# untitled.net
KiCad netlist of a schematic drawn in EAGLE
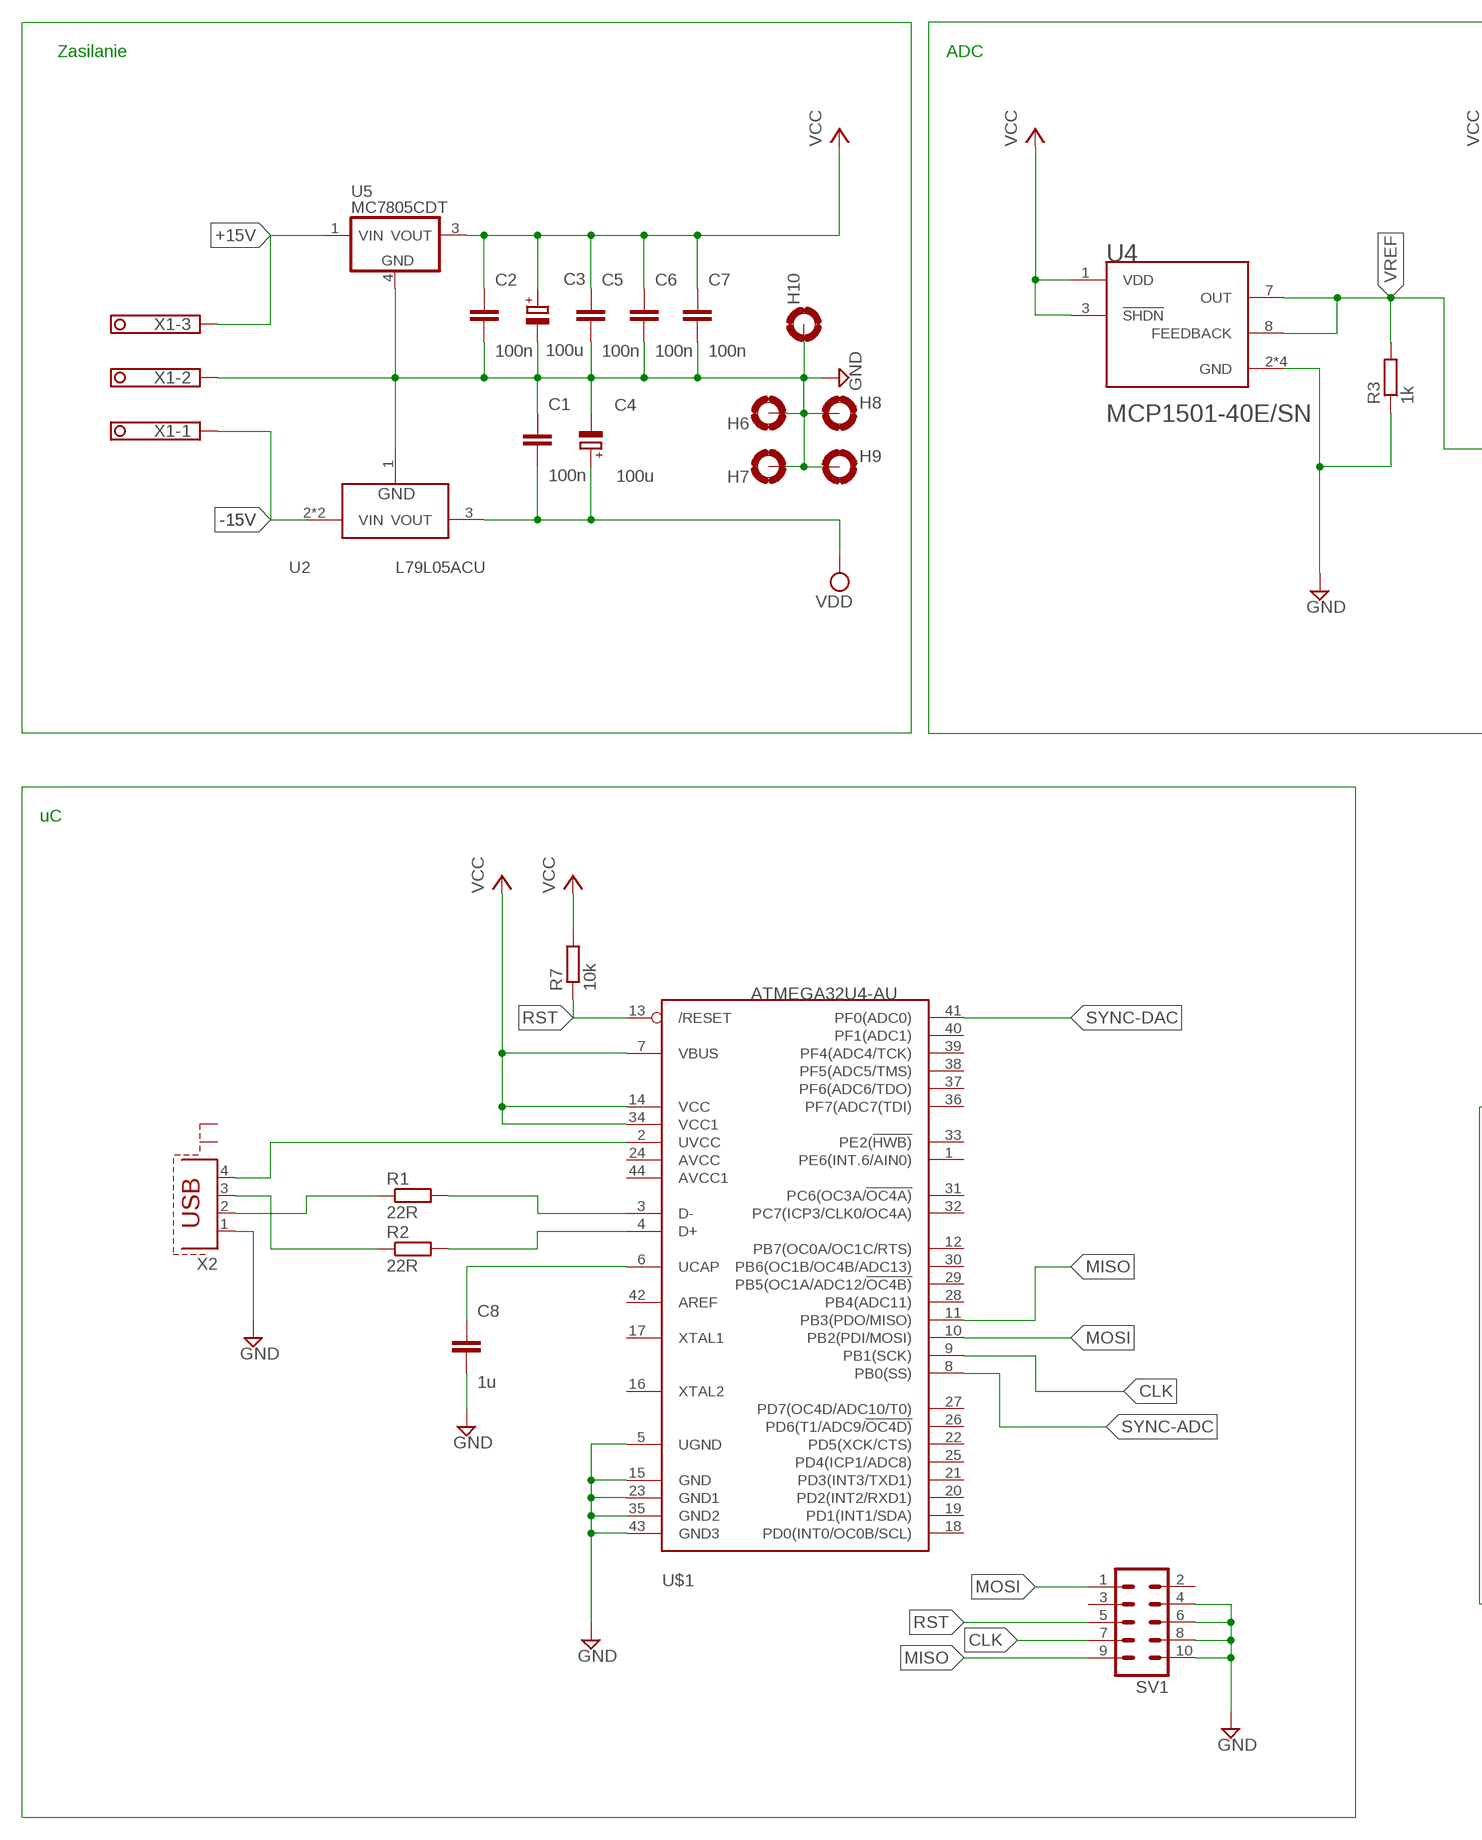
[diagram p0: schematic, sheet 1, part 1 of 2]
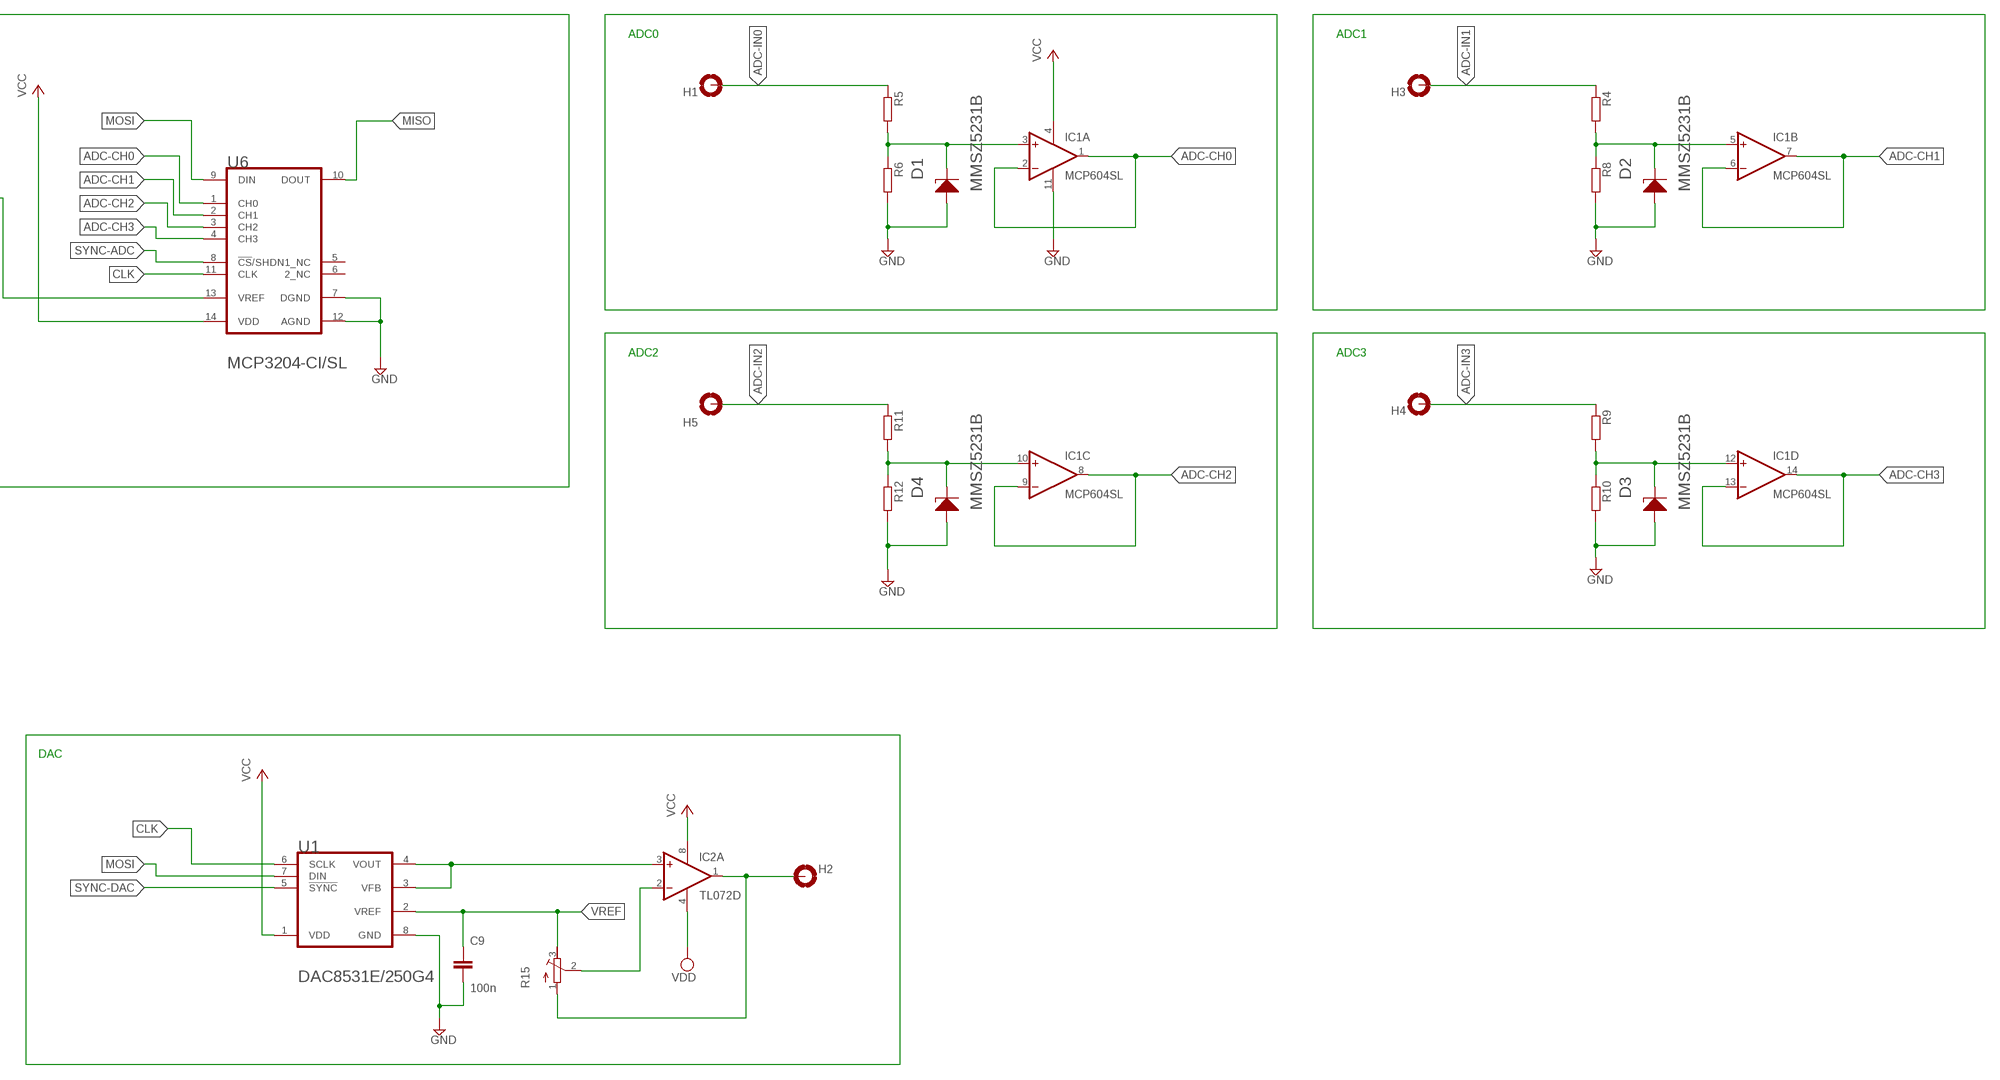
[diagram p1: schematic, sheet 1, part 2 of 2]

(export (version "E")
  (design (tool "Eeschema 10.0.6"))
  (components
    (comp (ref "C1")
      (value "100n")
      (footprint "eagle-import:C0805K")
      (libsource (lib "eagle-import") (part "C-EUC0805K"))
    )
    (comp (ref "C2")
      (value "100n")
      (footprint "eagle-import:C0805K")
      (libsource (lib "eagle-import") (part "C-EUC0805K"))
    )
    (comp (ref "C3")
      (value "100u")
      (footprint "eagle-import:153CLV-1014")
      (libsource (lib "eagle-import") (part "CPOL-EU153CLV-1014"))
    )
    (comp (ref "C4")
      (value "100u")
      (footprint "eagle-import:153CLV-1014")
      (libsource (lib "eagle-import") (part "CPOL-EU153CLV-1014"))
    )
    (comp (ref "C5")
      (value "100n")
      (footprint "eagle-import:C0805K")
      (libsource (lib "eagle-import") (part "C-EUC0805K"))
    )
    (comp (ref "C6")
      (value "100n")
      (footprint "eagle-import:C0805K")
      (libsource (lib "eagle-import") (part "C-EUC0805K"))
    )
    (comp (ref "C7")
      (value "100n")
      (footprint "eagle-import:C0805K")
      (libsource (lib "eagle-import") (part "C-EUC0805K"))
    )
    (comp (ref "C8")
      (value "1u")
      (footprint "eagle-import:C0805K")
      (libsource (lib "eagle-import") (part "C-EUC0805K"))
    )
    (comp (ref "C9")
      (value "100n")
      (footprint "eagle-import:C0805K")
      (libsource (lib "eagle-import") (part "C-EUC0805K"))
    )
    (comp (ref "D1")
      (value "MMSZ5231BVISHAY_SEMICONDUCTOR_MMSZ5231B-E3-08_0_0")
      (footprint "eagle-import:VISHAY_SEMICONDUCTOR_MMSZ5231B-E3-08_0")
      (fields
        (field (name "MF") "Vishay Semiconductor")
        (field (name "MPN") "MMSZ5231B-E3-08")
        (field (name "TOLERANCE") "+/- 5%")
      )
      (libsource (lib "eagle-import") (part "MMSZ5231BVISHAY_SEMICONDUCTOR_MMSZ5231B-E3-08_0_0"))
    )
    (comp (ref "D2")
      (value "MMSZ5231BVISHAY_SEMICONDUCTOR_MMSZ5231B-E3-08_0_0")
      (footprint "eagle-import:VISHAY_SEMICONDUCTOR_MMSZ5231B-E3-08_0")
      (fields
        (field (name "MF") "Vishay Semiconductor")
        (field (name "MPN") "MMSZ5231B-E3-08")
        (field (name "TOLERANCE") "+/- 5%")
      )
      (libsource (lib "eagle-import") (part "MMSZ5231BVISHAY_SEMICONDUCTOR_MMSZ5231B-E3-08_0_0"))
    )
    (comp (ref "D3")
      (value "MMSZ5231BVISHAY_SEMICONDUCTOR_MMSZ5231B-E3-08_0_0")
      (footprint "eagle-import:VISHAY_SEMICONDUCTOR_MMSZ5231B-E3-08_0")
      (fields
        (field (name "MF") "Vishay Semiconductor")
        (field (name "MPN") "MMSZ5231B-E3-08")
        (field (name "TOLERANCE") "+/- 5%")
      )
      (libsource (lib "eagle-import") (part "MMSZ5231BVISHAY_SEMICONDUCTOR_MMSZ5231B-E3-08_0_0"))
    )
    (comp (ref "D4")
      (value "MMSZ5231BVISHAY_SEMICONDUCTOR_MMSZ5231B-E3-08_0_0")
      (footprint "eagle-import:VISHAY_SEMICONDUCTOR_MMSZ5231B-E3-08_0")
      (fields
        (field (name "MF") "Vishay Semiconductor")
        (field (name "MPN") "MMSZ5231B-E3-08")
        (field (name "TOLERANCE") "+/- 5%")
      )
      (libsource (lib "eagle-import") (part "MMSZ5231BVISHAY_SEMICONDUCTOR_MMSZ5231B-E3-08_0_0"))
    )
    (comp (ref "H1")
      (value "MOUNT-PAD-ROUND2.8")
      (footprint "eagle-import:2,8-PAD")
      (libsource (lib "eagle-import") (part "MOUNT-PAD-ROUND2.8"))
    )
    (comp (ref "H2")
      (value "MOUNT-PAD-ROUND2.8")
      (footprint "eagle-import:2,8-PAD")
      (libsource (lib "eagle-import") (part "MOUNT-PAD-ROUND2.8"))
    )
    (comp (ref "H3")
      (value "MOUNT-PAD-ROUND2.8")
      (footprint "eagle-import:2,8-PAD")
      (libsource (lib "eagle-import") (part "MOUNT-PAD-ROUND2.8"))
    )
    (comp (ref "H4")
      (value "MOUNT-PAD-ROUND2.8")
      (footprint "eagle-import:2,8-PAD")
      (libsource (lib "eagle-import") (part "MOUNT-PAD-ROUND2.8"))
    )
    (comp (ref "H5")
      (value "MOUNT-PAD-ROUND2.8")
      (footprint "eagle-import:2,8-PAD")
      (libsource (lib "eagle-import") (part "MOUNT-PAD-ROUND2.8"))
    )
    (comp (ref "H6")
      (value "MOUNT-PAD-ROUND2.8")
      (footprint "eagle-import:2,8-PAD")
      (libsource (lib "eagle-import") (part "MOUNT-PAD-ROUND2.8"))
    )
    (comp (ref "H7")
      (value "MOUNT-PAD-ROUND2.8")
      (footprint "eagle-import:2,8-PAD")
      (libsource (lib "eagle-import") (part "MOUNT-PAD-ROUND2.8"))
    )
    (comp (ref "H8")
      (value "MOUNT-PAD-ROUND2.8")
      (footprint "eagle-import:2,8-PAD")
      (libsource (lib "eagle-import") (part "MOUNT-PAD-ROUND2.8"))
    )
    (comp (ref "H9")
      (value "MOUNT-PAD-ROUND2.8")
      (footprint "eagle-import:2,8-PAD")
      (libsource (lib "eagle-import") (part "MOUNT-PAD-ROUND2.8"))
    )
    (comp (ref "H10")
      (value "MOUNT-PAD-ROUND2.8")
      (footprint "eagle-import:2,8-PAD")
      (libsource (lib "eagle-import") (part "MOUNT-PAD-ROUND2.8"))
    )
    (comp (ref "IC1")
      (value "MCP604SL")
      (footprint "eagle-import:SO14")
      (libsource (lib "eagle-import") (part "MCP604SL"))
    )
    (comp (ref "IC2")
      (value "TL072D")
      (footprint "eagle-import:SO08")
      (fields (field (name "SPICEPREFIX") "J"))
      (libsource (lib "eagle-import") (part "TL072D"))
    )
    (comp (ref "R1")
      (value "22R")
      (footprint "eagle-import:R1206")
      (libsource (lib "eagle-import") (part "R-EU_R1206"))
    )
    (comp (ref "R2")
      (value "22R")
      (footprint "eagle-import:R1206")
      (libsource (lib "eagle-import") (part "R-EU_R1206"))
    )
    (comp (ref "R3")
      (value "1k")
      (footprint "eagle-import:M1206")
      (libsource (lib "eagle-import") (part "R-EU_M1206"))
    )
    (comp (ref "R4")
      (value "R-EU_M1206")
      (footprint "eagle-import:M1206")
      (libsource (lib "eagle-import") (part "R-EU_M1206"))
    )
    (comp (ref "R5")
      (value "R-EU_M1206")
      (footprint "eagle-import:M1206")
      (libsource (lib "eagle-import") (part "R-EU_M1206"))
    )
    (comp (ref "R6")
      (value "R-EU_M1206")
      (footprint "eagle-import:M1206")
      (libsource (lib "eagle-import") (part "R-EU_M1206"))
    )
    (comp (ref "R7")
      (value "10k")
      (footprint "eagle-import:M1206")
      (libsource (lib "eagle-import") (part "R-EU_M1206"))
    )
    (comp (ref "R8")
      (value "R-EU_M1206")
      (footprint "eagle-import:M1206")
      (libsource (lib "eagle-import") (part "R-EU_M1206"))
    )
    (comp (ref "R9")
      (value "R-EU_M1206")
      (footprint "eagle-import:M1206")
      (libsource (lib "eagle-import") (part "R-EU_M1206"))
    )
    (comp (ref "R10")
      (value "R-EU_M1206")
      (footprint "eagle-import:M1206")
      (libsource (lib "eagle-import") (part "R-EU_M1206"))
    )
    (comp (ref "R11")
      (value "R-EU_M1206")
      (footprint "eagle-import:M1206")
      (libsource (lib "eagle-import") (part "R-EU_M1206"))
    )
    (comp (ref "R12")
      (value "R-EU_M1206")
      (footprint "eagle-import:M1206")
      (libsource (lib "eagle-import") (part "R-EU_M1206"))
    )
    (comp (ref "R15")
      (value "R-TRIMM64Y")
      (footprint "eagle-import:RTRIM64Y")
      (libsource (lib "eagle-import") (part "R-TRIMM64Y"))
    )
    (comp (ref "SV1")
      (value "ML10")
      (footprint "eagle-import:ML10")
      (libsource (lib "eagle-import") (part "ML10"))
    )
    (comp (ref "U$1")
      (value "ATMEGA32U4-AU")
      (footprint "eagle-import:TQFP44")
      (libsource (lib "eagle-import") (part "ATMEGA32U4-AU"))
    )
    (comp (ref "U1")
      (value "TEXAS_INSTRUMENTS_DAC8531E-250G4TEXAS_INSTRUMENTS_DAC8531E-250G4_0_0")
      (footprint "eagle-import:TEXAS_INSTRUMENTS_DAC8531E-250G4_0")
      (fields (field (name "MF") "Texas Instruments") (field (name "MPN") "DAC8531E/250G4"))
      (libsource (lib "eagle-import") (part "TEXAS_INSTRUMENTS_DAC8531E-250G4TEXAS_INSTRUMENTS_DAC8531E-250G4_0_0"))
    )
    (comp (ref "U2")
      (value "L79L05ACUTRL79L05ACU")
      (footprint "eagle-import:L79L05ACUTR_1")
      (fields
        (field (name "MF") "STMicroelectronics")
        (field (name "MPN") "L79L05ACUTR")
        (field (name "SPICEPREFIX") "U")
      )
      (libsource (lib "eagle-import") (part "L79L05ACUTRL79L05ACU"))
    )
    (comp (ref "U4")
      (value "MCP1501-40E/SN")
      (footprint "eagle-import:SOIC127P600X175-8N")
      (fields (field (name "MF") "Microchip"))
      (libsource (lib "eagle-import") (part "MCP1501-40E/SN"))
    )
    (comp (ref "U5")
      (value "MC7805CDT")
      (footprint "eagle-import:DPAK-3")
      (libsource (lib "eagle-import") (part "MC78DT05C"))
    )
    (comp (ref "U6")
      (value "MCP3204-CI-SL")
      (footprint "eagle-import:SO14")
      (libsource (lib "eagle-import") (part "MCP3204-CI-SL"))
    )
    (comp (ref "X1")
      (value "1751251")
      (footprint "eagle-import:1751251")
      (libsource (lib "eagle-import") (part "1751251"))
    )
    (comp (ref "X2")
      (value "PN61729-S")
      (footprint "eagle-import:PN61729-S")
      (libsource (lib "eagle-import") (part "PN61729-S"))
    )
  )
  (nets
    (net (code "1") (name "+15V") (class "Default")
      (node (ref "U5") (pin "1") (pinfunction "VIN_1") (pintype "power_in"))
      (node (ref "X1") (pin "3") (pinfunction "K_3") (pintype "passive"))
    )
    (net (code "2") (name "-15V") (class "Default")
      (node (ref "U2") (pin "2") (pinfunction "VIN_2") (pintype "power_in"))
      (node (ref "U2") (pin "2-2") (pinfunction "VIN_2-2") (pintype "power_in"))
      (node (ref "X1") (pin "1") (pinfunction "K_1") (pintype "passive"))
    )
    (net (code "3") (name "ADC-CH0") (class "Default")
      (node (ref "IC1") (pin "1") (pinfunction "OUT_1") (pintype "output"))
      (node (ref "IC1") (pin "2") (pinfunction "-IN_2") (pintype "input"))
      (node (ref "U6") (pin "1") (pinfunction "CH0_1") (pintype "input"))
    )
    (net (code "4") (name "ADC-CH1") (class "Default")
      (node (ref "IC1") (pin "6") (pinfunction "-IN_6") (pintype "input"))
      (node (ref "IC1") (pin "7") (pinfunction "OUT_7") (pintype "output"))
      (node (ref "U6") (pin "2") (pinfunction "CH1_2") (pintype "input"))
    )
    (net (code "5") (name "ADC-CH2") (class "Default")
      (node (ref "IC1") (pin "8") (pinfunction "OUT_8") (pintype "output"))
      (node (ref "IC1") (pin "9") (pinfunction "-IN_9") (pintype "input"))
      (node (ref "U6") (pin "3") (pinfunction "CH2_3") (pintype "input"))
    )
    (net (code "6") (name "ADC-CH3") (class "Default")
      (node (ref "IC1") (pin "13") (pinfunction "-IN_13") (pintype "input"))
      (node (ref "IC1") (pin "14") (pinfunction "OUT_14") (pintype "output"))
      (node (ref "U6") (pin "4") (pinfunction "CH3_4") (pintype "input"))
    )
    (net (code "7") (name "ADC-IN0") (class "Default")
      (node (ref "H1") (pin "B2,8") (pinfunction "MOUNT_B2,8") (pintype "passive"))
      (node (ref "R5") (pin "1") (pinfunction "1_1") (pintype "passive"))
    )
    (net (code "8") (name "ADC-IN1") (class "Default")
      (node (ref "H3") (pin "B2,8") (pinfunction "MOUNT_B2,8") (pintype "passive"))
      (node (ref "R4") (pin "1") (pinfunction "1_1") (pintype "passive"))
    )
    (net (code "9") (name "ADC-IN2") (class "Default")
      (node (ref "H5") (pin "B2,8") (pinfunction "MOUNT_B2,8") (pintype "passive"))
      (node (ref "R11") (pin "1") (pinfunction "1_1") (pintype "passive"))
    )
    (net (code "10") (name "ADC-IN3") (class "Default")
      (node (ref "H4") (pin "B2,8") (pinfunction "MOUNT_B2,8") (pintype "passive"))
      (node (ref "R9") (pin "1") (pinfunction "1_1") (pintype "passive"))
    )
    (net (code "11") (name "CLK") (class "Default")
      (node (ref "SV1") (pin "7") (pinfunction "7_7") (pintype "passive"))
      (node (ref "U$1") (pin "9") (pinfunction "PB1(SCK)_9") (pintype "bidirectional"))
      (node (ref "U1") (pin "6") (pinfunction "SCLK_6") (pintype "input"))
      (node (ref "U6") (pin "11") (pinfunction "CLK_11") (pintype "input"))
    )
    (net (code "12") (name "GND") (class "Default")
      (node (ref "C1") (pin "1") (pinfunction "1_1") (pintype "passive"))
      (node (ref "C2") (pin "2") (pinfunction "2_2") (pintype "passive"))
      (node (ref "C3") (pin "-") (pinfunction "-_-") (pintype "passive"))
      (node (ref "C4") (pin "-") (pinfunction "-_-") (pintype "passive"))
      (node (ref "C5") (pin "2") (pinfunction "2_2") (pintype "passive"))
      (node (ref "C6") (pin "2") (pinfunction "2_2") (pintype "passive"))
      (node (ref "C7") (pin "2") (pinfunction "2_2") (pintype "passive"))
      (node (ref "C8") (pin "2") (pinfunction "2_2") (pintype "passive"))
      (node (ref "C9") (pin "2") (pinfunction "2_2") (pintype "passive"))
      (node (ref "D1") (pin "1") (pinfunction "A_1") (pintype "passive"))
      (node (ref "D2") (pin "1") (pinfunction "A_1") (pintype "passive"))
      (node (ref "D3") (pin "1") (pinfunction "A_1") (pintype "passive"))
      (node (ref "D4") (pin "1") (pinfunction "A_1") (pintype "passive"))
      (node (ref "H10") (pin "B2,8") (pinfunction "MOUNT_B2,8") (pintype "passive"))
      (node (ref "H6") (pin "B2,8") (pinfunction "MOUNT_B2,8") (pintype "passive"))
      (node (ref "H7") (pin "B2,8") (pinfunction "MOUNT_B2,8") (pintype "passive"))
      (node (ref "H8") (pin "B2,8") (pinfunction "MOUNT_B2,8") (pintype "passive"))
      (node (ref "H9") (pin "B2,8") (pinfunction "MOUNT_B2,8") (pintype "passive"))
      (node (ref "IC1") (pin "11") (pinfunction "V-_11") (pintype "power_in"))
      (node (ref "R10") (pin "2") (pinfunction "2_2") (pintype "passive"))
      (node (ref "R12") (pin "2") (pinfunction "2_2") (pintype "passive"))
      (node (ref "R3") (pin "1") (pinfunction "1_1") (pintype "passive"))
      (node (ref "R6") (pin "2") (pinfunction "2_2") (pintype "passive"))
      (node (ref "R8") (pin "2") (pinfunction "2_2") (pintype "passive"))
      (node (ref "SV1") (pin "10") (pinfunction "10_10") (pintype "passive"))
      (node (ref "SV1") (pin "4") (pinfunction "4_4") (pintype "passive"))
      (node (ref "SV1") (pin "6") (pinfunction "6_6") (pintype "passive"))
      (node (ref "SV1") (pin "8") (pinfunction "8_8") (pintype "passive"))
      (node (ref "U$1") (pin "15") (pinfunction "GND_15") (pintype "bidirectional"))
      (node (ref "U$1") (pin "23") (pinfunction "GND1_23") (pintype "bidirectional"))
      (node (ref "U$1") (pin "35") (pinfunction "GND2_35") (pintype "bidirectional"))
      (node (ref "U$1") (pin "43") (pinfunction "GND3_43") (pintype "bidirectional"))
      (node (ref "U$1") (pin "5") (pinfunction "UGND_5") (pintype "bidirectional"))
      (node (ref "U1") (pin "8") (pinfunction "GND_8") (pintype "power_in"))
      (node (ref "U2") (pin "1") (pinfunction "GND_1") (pintype "power_in"))
      (node (ref "U4") (pin "2") (pinfunction "GND_2") (pintype "passive"))
      (node (ref "U4") (pin "4") (pinfunction "GND_4") (pintype "passive"))
      (node (ref "U4") (pin "5") (pinfunction "GND_5") (pintype "passive"))
      (node (ref "U4") (pin "6") (pinfunction "GND_6") (pintype "passive"))
      (node (ref "U5") (pin "4") (pinfunction "GND_4") (pintype "power_in"))
      (node (ref "U6") (pin "12") (pinfunction "AGND_12") (pintype "power_in"))
      (node (ref "U6") (pin "7") (pinfunction "DGND_7") (pintype "power_in"))
      (node (ref "X1") (pin "2") (pinfunction "K_2") (pintype "passive"))
      (node (ref "X2") (pin "1") (pinfunction "1_1") (pintype "passive"))
    )
    (net (code "13") (name "MISO") (class "Default")
      (node (ref "SV1") (pin "9") (pinfunction "9_9") (pintype "passive"))
      (node (ref "U$1") (pin "11") (pinfunction "PB3(PDO/MISO)_11") (pintype "bidirectional"))
      (node (ref "U6") (pin "10") (pinfunction "DOUT_10") (pintype "tri_state"))
    )
    (net (code "14") (name "MOSI") (class "Default")
      (node (ref "SV1") (pin "1") (pinfunction "1_1") (pintype "passive"))
      (node (ref "U$1") (pin "10") (pinfunction "PB2(PDI/MOSI)_10") (pintype "bidirectional"))
      (node (ref "U1") (pin "7") (pinfunction "DIN_7") (pintype "input"))
      (node (ref "U6") (pin "9") (pinfunction "DIN_9") (pintype "input"))
    )
    (net (code "15") (name "Net-(D1-K)") (class "Default")
      (node (ref "D1") (pin "2") (pinfunction "K_2") (pintype "passive"))
      (node (ref "IC1") (pin "3") (pinfunction "+IN_3") (pintype "input"))
      (node (ref "R5") (pin "2") (pinfunction "2_2") (pintype "passive"))
      (node (ref "R6") (pin "1") (pinfunction "1_1") (pintype "passive"))
    )
    (net (code "16") (name "Net-(D2-K)") (class "Default")
      (node (ref "D2") (pin "2") (pinfunction "K_2") (pintype "passive"))
      (node (ref "IC1") (pin "5") (pinfunction "+IN_5") (pintype "input"))
      (node (ref "R4") (pin "2") (pinfunction "2_2") (pintype "passive"))
      (node (ref "R8") (pin "1") (pinfunction "1_1") (pintype "passive"))
    )
    (net (code "17") (name "Net-(D3-K)") (class "Default")
      (node (ref "D3") (pin "2") (pinfunction "K_2") (pintype "passive"))
      (node (ref "IC1") (pin "12") (pinfunction "+IN_12") (pintype "input"))
      (node (ref "R10") (pin "1") (pinfunction "1_1") (pintype "passive"))
      (node (ref "R9") (pin "2") (pinfunction "2_2") (pintype "passive"))
    )
    (net (code "18") (name "Net-(D4-K)") (class "Default")
      (node (ref "D4") (pin "2") (pinfunction "K_2") (pintype "passive"))
      (node (ref "IC1") (pin "10") (pinfunction "+IN_10") (pintype "input"))
      (node (ref "R11") (pin "2") (pinfunction "2_2") (pintype "passive"))
      (node (ref "R12") (pin "1") (pinfunction "1_1") (pintype "passive"))
    )
    (net (code "19") (name "Net-(H2-MOUNT)") (class "Default")
      (node (ref "H2") (pin "B2,8") (pinfunction "MOUNT_B2,8") (pintype "passive"))
      (node (ref "IC2") (pin "1") (pinfunction "OUT_1") (pintype "output"))
      (node (ref "R15") (pin "1") (pinfunction "A_1") (pintype "passive"))
    )
    (net (code "20") (name "Net-(IC2A-+IN)") (class "Default")
      (node (ref "IC2") (pin "3") (pinfunction "+IN_3") (pintype "input"))
      (node (ref "U1") (pin "3") (pinfunction "VFB_3") (pintype "input"))
      (node (ref "U1") (pin "4") (pinfunction "VOUT_4") (pintype "tri_state"))
    )
    (net (code "21") (name "Net-(IC2A--IN)") (class "Default")
      (node (ref "IC2") (pin "2") (pinfunction "-IN_2") (pintype "input"))
      (node (ref "R15") (pin "2") (pinfunction "S_2") (pintype "passive"))
    )
    (net (code "22") (name "Net-(R1-Pad1)") (class "Default")
      (node (ref "R1") (pin "1") (pinfunction "1_1") (pintype "passive"))
      (node (ref "X2") (pin "2") (pinfunction "2_2") (pintype "passive"))
    )
    (net (code "23") (name "Net-(R2-Pad1)") (class "Default")
      (node (ref "R2") (pin "1") (pinfunction "1_1") (pintype "passive"))
      (node (ref "X2") (pin "3") (pinfunction "3_3") (pintype "passive"))
    )
    (net (code "24") (name "Net-(U$1-D+)") (class "Default")
      (node (ref "R2") (pin "2") (pinfunction "2_2") (pintype "passive"))
      (node (ref "U$1") (pin "4") (pinfunction "D+_4") (pintype "bidirectional"))
    )
    (net (code "25") (name "Net-(U$1-D-)") (class "Default")
      (node (ref "R1") (pin "2") (pinfunction "2_2") (pintype "passive"))
      (node (ref "U$1") (pin "3") (pinfunction "D-_3") (pintype "bidirectional"))
    )
    (net (code "26") (name "Net-(U$1-UCAP)") (class "Default")
      (node (ref "C8") (pin "1") (pinfunction "1_1") (pintype "passive"))
      (node (ref "U$1") (pin "6") (pinfunction "UCAP_6") (pintype "bidirectional"))
    )
    (net (code "27") (name "Net-(U$1-UVCC)") (class "Default")
      (node (ref "U$1") (pin "2") (pinfunction "UVCC_2") (pintype "bidirectional"))
      (node (ref "X2") (pin "4") (pinfunction "4_4") (pintype "passive"))
    )
    (net (code "28") (name "RST") (class "Default")
      (node (ref "R7") (pin "1") (pinfunction "1_1") (pintype "passive"))
      (node (ref "SV1") (pin "5") (pinfunction "5_5") (pintype "passive"))
      (node (ref "U$1") (pin "13") (pinfunction "/RESET_13") (pintype "bidirectional"))
    )
    (net (code "29") (name "SYNC-ADC") (class "Default")
      (node (ref "U$1") (pin "8") (pinfunction "PB0(SS)_8") (pintype "bidirectional"))
      (node (ref "U6") (pin "8") (pinfunction "~{CS}/SHDN_8") (pintype "input"))
    )
    (net (code "30") (name "SYNC-DAC") (class "Default")
      (node (ref "U$1") (pin "41") (pinfunction "PF0(ADC0)_41") (pintype "bidirectional"))
      (node (ref "U1") (pin "5") (pinfunction "~{SYNC}_5") (pintype "input"))
    )
    (net (code "31") (name "VCC") (class "Default")
      (node (ref "C2") (pin "1") (pinfunction "1_1") (pintype "passive"))
      (node (ref "C3") (pin "+") (pinfunction "+_+") (pintype "passive"))
      (node (ref "C5") (pin "1") (pinfunction "1_1") (pintype "passive"))
      (node (ref "C6") (pin "1") (pinfunction "1_1") (pintype "passive"))
      (node (ref "C7") (pin "1") (pinfunction "1_1") (pintype "passive"))
      (node (ref "IC1") (pin "4") (pinfunction "V+_4") (pintype "power_in"))
      (node (ref "IC2") (pin "8") (pinfunction "V+_8") (pintype "power_in"))
      (node (ref "R7") (pin "2") (pinfunction "2_2") (pintype "passive"))
      (node (ref "U$1") (pin "14") (pinfunction "VCC_14") (pintype "bidirectional"))
      (node (ref "U$1") (pin "34") (pinfunction "VCC1_34") (pintype "bidirectional"))
      (node (ref "U$1") (pin "7") (pinfunction "VBUS_7") (pintype "bidirectional"))
      (node (ref "U1") (pin "1") (pinfunction "VDD_1") (pintype "power_in"))
      (node (ref "U4") (pin "1") (pinfunction "VDD_1") (pintype "power_in"))
      (node (ref "U4") (pin "3") (pinfunction "~{SHDN}_3") (pintype "input"))
      (node (ref "U5") (pin "3") (pinfunction "VOUT_3") (pintype "power_in"))
      (node (ref "U6") (pin "14") (pinfunction "VDD_14") (pintype "power_in"))
    )
    (net (code "32") (name "VDD") (class "Default")
      (node (ref "C1") (pin "2") (pinfunction "2_2") (pintype "passive"))
      (node (ref "C4") (pin "+") (pinfunction "+_+") (pintype "passive"))
      (node (ref "IC2") (pin "4") (pinfunction "V-_4") (pintype "power_in"))
      (node (ref "U2") (pin "3") (pinfunction "VOUT_3") (pintype "power_in"))
    )
    (net (code "33") (name "VREF") (class "Default")
      (node (ref "C9") (pin "1") (pinfunction "1_1") (pintype "passive"))
      (node (ref "R15") (pin "3") (pinfunction "E_3") (pintype "passive"))
      (node (ref "R3") (pin "2") (pinfunction "2_2") (pintype "passive"))
      (node (ref "U1") (pin "2") (pinfunction "VREF_2") (pintype "input"))
      (node (ref "U4") (pin "7") (pinfunction "OUT_7") (pintype "output"))
      (node (ref "U4") (pin "8") (pinfunction "FEEDBACK_8") (pintype "passive"))
      (node (ref "U6") (pin "13") (pinfunction "VREF_13") (pintype "input"))
    )
    (net (code "34") (name "unconnected-(SV1-Pad2)") (class "Default")
      (node (ref "SV1") (pin "2") (pinfunction "2_2") (pintype "passive"))
    )
    (net (code "35") (name "unconnected-(SV1-Pad3)") (class "Default")
      (node (ref "SV1") (pin "3") (pinfunction "3_3") (pintype "passive"))
    )
    (net (code "36") (name "unconnected-(U$1-AREF-Pad42)") (class "Default")
      (node (ref "U$1") (pin "42") (pinfunction "AREF_42") (pintype "bidirectional"))
    )
    (net (code "37") (name "unconnected-(U$1-AVCC-Pad24)") (class "Default")
      (node (ref "U$1") (pin "24") (pinfunction "AVCC_24") (pintype "bidirectional"))
    )
    (net (code "38") (name "unconnected-(U$1-AVCC1-Pad44)") (class "Default")
      (node (ref "U$1") (pin "44") (pinfunction "AVCC1_44") (pintype "bidirectional"))
    )
    (net (code "39") (name "unconnected-(U$1-PB4(ADC11)-Pad28)") (class "Default")
      (node (ref "U$1") (pin "28") (pinfunction "PB4(ADC11)_28") (pintype "bidirectional"))
    )
    (net (code "40") (name "unconnected-(U$1-PB5(OC1A{slash}ADC12{slash}~{OC4B})-Pad29)") (class "Default")
      (node (ref "U$1") (pin "29") (pinfunction "PB5(OC1A/ADC12/~{OC4B})_29") (pintype "bidirectional"))
    )
    (net (code "41") (name "unconnected-(U$1-PB6(OC1B{slash}OC4B{slash}ADC13)-Pad30)") (class "Default")
      (node (ref "U$1") (pin "30") (pinfunction "PB6(OC1B/OC4B/ADC13)_30") (pintype "bidirectional"))
    )
    (net (code "42") (name "unconnected-(U$1-PB7(OC0A{slash}OC1C{slash}RTS)-Pad12)") (class "Default")
      (node (ref "U$1") (pin "12") (pinfunction "PB7(OC0A/OC1C/RTS)_12") (pintype "bidirectional"))
    )
    (net (code "43") (name "unconnected-(U$1-PC6(OC3A{slash}~{OC4A})-Pad31)") (class "Default")
      (node (ref "U$1") (pin "31") (pinfunction "PC6(OC3A/~{OC4A})_31") (pintype "bidirectional"))
    )
    (net (code "44") (name "unconnected-(U$1-PC7(ICP3{slash}CLK0{slash}OC4A)-Pad32)") (class "Default")
      (node (ref "U$1") (pin "32") (pinfunction "PC7(ICP3/CLK0/OC4A)_32") (pintype "bidirectional"))
    )
    (net (code "45") (name "unconnected-(U$1-PD0(INT0{slash}OC0B{slash}SCL)-Pad18)") (class "Default")
      (node (ref "U$1") (pin "18") (pinfunction "PD0(INT0/OC0B/SCL)_18") (pintype "bidirectional"))
    )
    (net (code "46") (name "unconnected-(U$1-PD1(INT1{slash}SDA)-Pad19)") (class "Default")
      (node (ref "U$1") (pin "19") (pinfunction "PD1(INT1/SDA)_19") (pintype "bidirectional"))
    )
    (net (code "47") (name "unconnected-(U$1-PD2(INT2{slash}RXD1)-Pad20)") (class "Default")
      (node (ref "U$1") (pin "20") (pinfunction "PD2(INT2/RXD1)_20") (pintype "bidirectional"))
    )
    (net (code "48") (name "unconnected-(U$1-PD3(INT3{slash}TXD1)-Pad21)") (class "Default")
      (node (ref "U$1") (pin "21") (pinfunction "PD3(INT3/TXD1)_21") (pintype "bidirectional"))
    )
    (net (code "49") (name "unconnected-(U$1-PD4(ICP1{slash}ADC8)-Pad25)") (class "Default")
      (node (ref "U$1") (pin "25") (pinfunction "PD4(ICP1/ADC8)_25") (pintype "bidirectional"))
    )
    (net (code "50") (name "unconnected-(U$1-PD5(XCK{slash}CTS)-Pad22)") (class "Default")
      (node (ref "U$1") (pin "22") (pinfunction "PD5(XCK/CTS)_22") (pintype "bidirectional"))
    )
    (net (code "51") (name "unconnected-(U$1-PD6(T1{slash}ADC9{slash}~{OC4D})-Pad26)") (class "Default")
      (node (ref "U$1") (pin "26") (pinfunction "PD6(T1/ADC9/~{OC4D})_26") (pintype "bidirectional"))
    )
    (net (code "52") (name "unconnected-(U$1-PD7(OC4D{slash}ADC10{slash}T0)-Pad27)") (class "Default")
      (node (ref "U$1") (pin "27") (pinfunction "PD7(OC4D/ADC10/T0)_27") (pintype "bidirectional"))
    )
    (net (code "53") (name "unconnected-(U$1-PE2(~{HWB})-Pad33)") (class "Default")
      (node (ref "U$1") (pin "33") (pinfunction "PE2(~{HWB})_33") (pintype "bidirectional"))
    )
    (net (code "54") (name "unconnected-(U$1-PE6(INT.6{slash}AIN0)-Pad1)") (class "Default")
      (node (ref "U$1") (pin "1") (pinfunction "PE6(INT.6/AIN0)_1") (pintype "bidirectional"))
    )
    (net (code "55") (name "unconnected-(U$1-PF1(ADC1)-Pad40)") (class "Default")
      (node (ref "U$1") (pin "40") (pinfunction "PF1(ADC1)_40") (pintype "bidirectional"))
    )
    (net (code "56") (name "unconnected-(U$1-PF4(ADC4{slash}TCK)-Pad39)") (class "Default")
      (node (ref "U$1") (pin "39") (pinfunction "PF4(ADC4/TCK)_39") (pintype "bidirectional"))
    )
    (net (code "57") (name "unconnected-(U$1-PF5(ADC5{slash}TMS)-Pad38)") (class "Default")
      (node (ref "U$1") (pin "38") (pinfunction "PF5(ADC5/TMS)_38") (pintype "bidirectional"))
    )
    (net (code "58") (name "unconnected-(U$1-PF6(ADC6{slash}TDO)-Pad37)") (class "Default")
      (node (ref "U$1") (pin "37") (pinfunction "PF6(ADC6/TDO)_37") (pintype "bidirectional"))
    )
    (net (code "59") (name "unconnected-(U$1-PF7(ADC7(TDI)-Pad36)") (class "Default")
      (node (ref "U$1") (pin "36") (pinfunction "PF7(ADC7(TDI)_36") (pintype "bidirectional"))
    )
    (net (code "60") (name "unconnected-(U$1-XTAL1-Pad17)") (class "Default")
      (node (ref "U$1") (pin "17") (pinfunction "XTAL1_17") (pintype "bidirectional"))
    )
    (net (code "61") (name "unconnected-(U$1-XTAL2-Pad16)") (class "Default")
      (node (ref "U$1") (pin "16") (pinfunction "XTAL2_16") (pintype "bidirectional"))
    )
    (net (code "62") (name "unconnected-(U6-1_NC-Pad5)") (class "Default")
      (node (ref "U6") (pin "5") (pinfunction "1_NC_5") (pintype "passive"))
    )
    (net (code "63") (name "unconnected-(U6-2_NC-Pad6)") (class "Default")
      (node (ref "U6") (pin "6") (pinfunction "2_NC_6") (pintype "passive"))
    )
    (net (code "64") (name "unconnected-(X2-PadS1)") (class "Default")
      (node (ref "X2") (pin "S1") (pinfunction "S1_S1") (pintype "passive"))
    )
    (net (code "65") (name "unconnected-(X2-PadS2)") (class "Default")
      (node (ref "X2") (pin "S2") (pinfunction "S2_S2") (pintype "passive"))
    )
  )
)
